# EAGLE.net
KiCad netlist of a schematic drawn in EAGLE
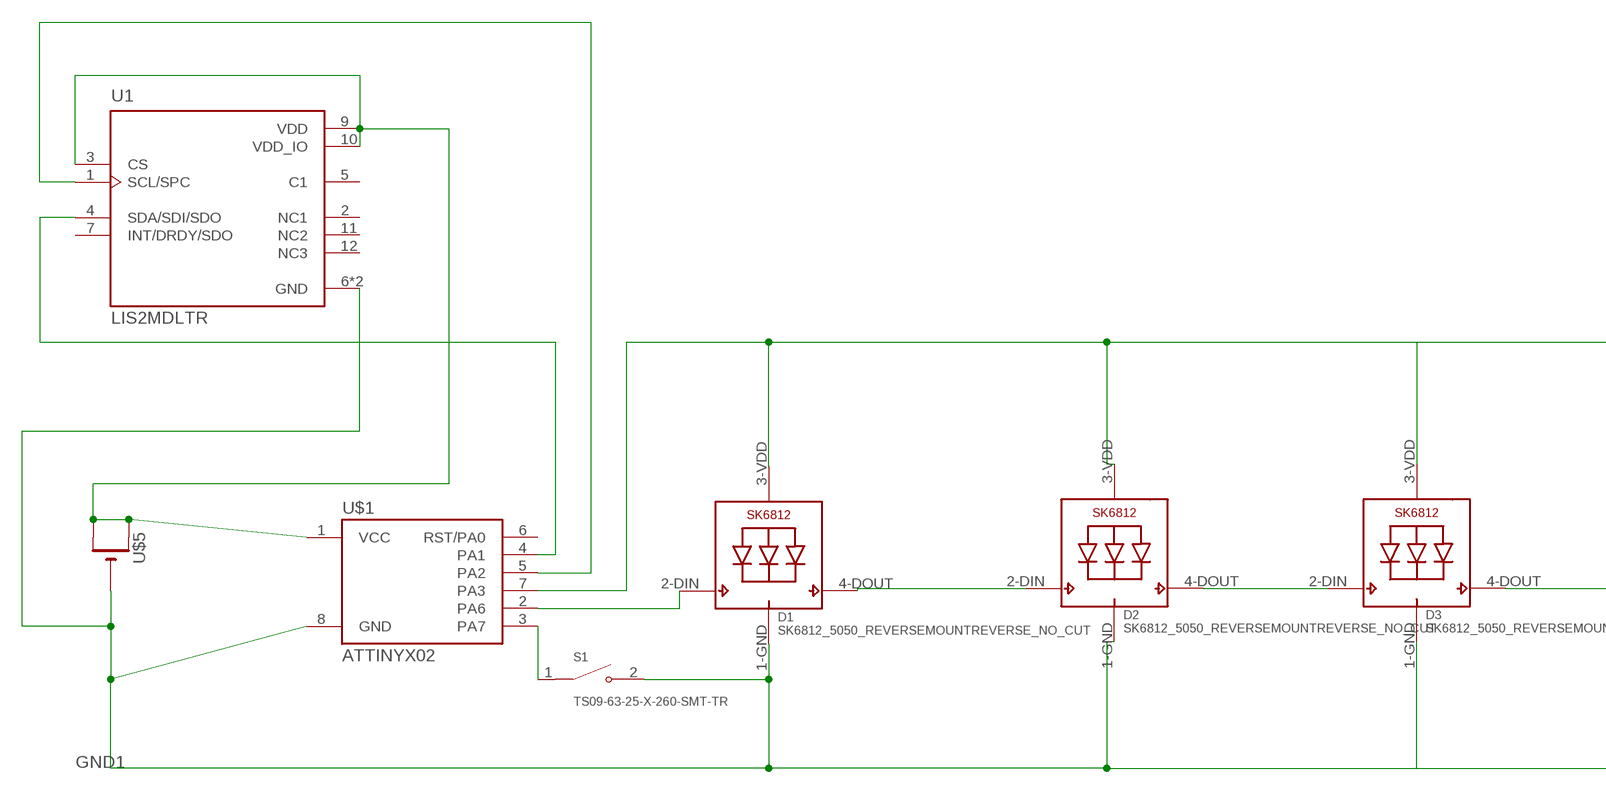
[diagram p0: schematic, sheet 1, part 1 of 2]
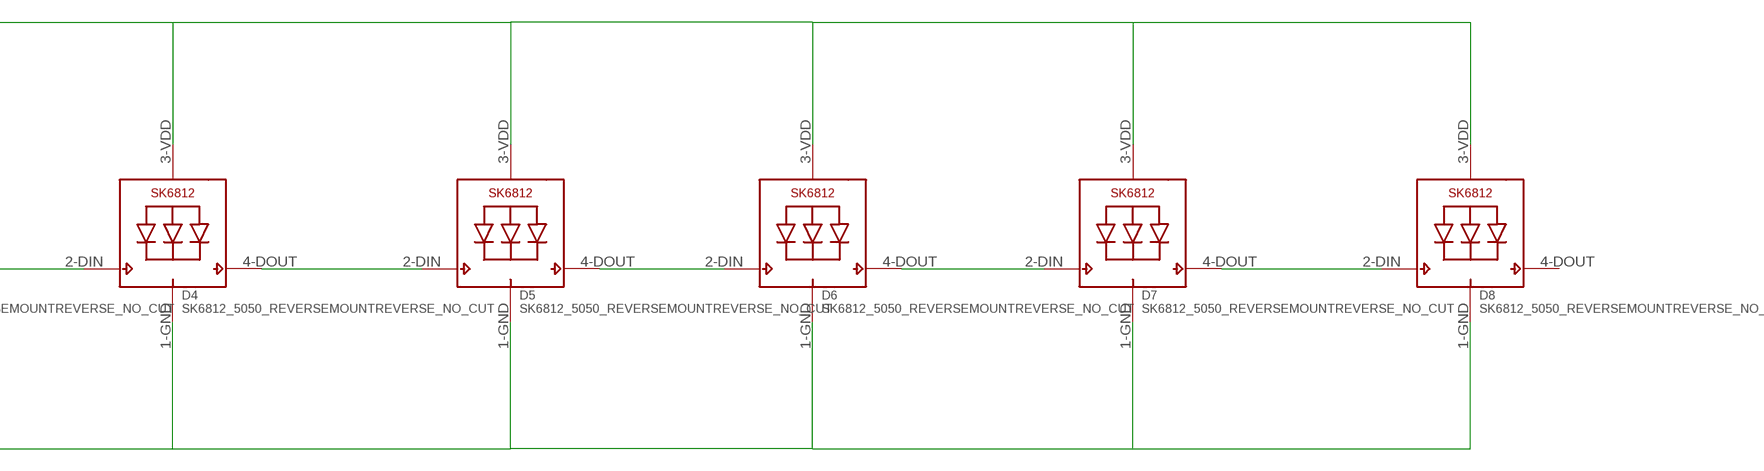
[diagram p1: schematic, sheet 1, part 2 of 2]

(export (version "E")
  (design (tool "Eeschema 10.0.6"))
  (components
    (comp (ref "D1")
      (value "SK6812_5050_REVERSEMOUNTREVERSE_NO_CUT")
      (footprint "eagle-import:SK6812_REVERSE_NO_CUT")
      (libsource (lib "eagle-import") (part "SK6812_5050_REVERSEMOUNTREVERSE_NO_CUT"))
    )
    (comp (ref "D2")
      (value "SK6812_5050_REVERSEMOUNTREVERSE_NO_CUT")
      (footprint "eagle-import:SK6812_REVERSE_NO_CUT")
      (libsource (lib "eagle-import") (part "SK6812_5050_REVERSEMOUNTREVERSE_NO_CUT"))
    )
    (comp (ref "D3")
      (value "SK6812_5050_REVERSEMOUNTREVERSE_NO_CUT")
      (footprint "eagle-import:SK6812_REVERSE_NO_CUT")
      (libsource (lib "eagle-import") (part "SK6812_5050_REVERSEMOUNTREVERSE_NO_CUT"))
    )
    (comp (ref "D4")
      (value "SK6812_5050_REVERSEMOUNTREVERSE_NO_CUT")
      (footprint "eagle-import:SK6812_REVERSE_NO_CUT")
      (libsource (lib "eagle-import") (part "SK6812_5050_REVERSEMOUNTREVERSE_NO_CUT"))
    )
    (comp (ref "D5")
      (value "SK6812_5050_REVERSEMOUNTREVERSE_NO_CUT")
      (footprint "eagle-import:SK6812_REVERSE_NO_CUT")
      (libsource (lib "eagle-import") (part "SK6812_5050_REVERSEMOUNTREVERSE_NO_CUT"))
    )
    (comp (ref "D6")
      (value "SK6812_5050_REVERSEMOUNTREVERSE_NO_CUT")
      (footprint "eagle-import:SK6812_REVERSE_NO_CUT")
      (libsource (lib "eagle-import") (part "SK6812_5050_REVERSEMOUNTREVERSE_NO_CUT"))
    )
    (comp (ref "D7")
      (value "SK6812_5050_REVERSEMOUNTREVERSE_NO_CUT")
      (footprint "eagle-import:SK6812_REVERSE_NO_CUT")
      (libsource (lib "eagle-import") (part "SK6812_5050_REVERSEMOUNTREVERSE_NO_CUT"))
    )
    (comp (ref "D8")
      (value "SK6812_5050_REVERSEMOUNTREVERSE_NO_CUT")
      (footprint "eagle-import:SK6812_REVERSE_NO_CUT")
      (libsource (lib "eagle-import") (part "SK6812_5050_REVERSEMOUNTREVERSE_NO_CUT"))
    )
    (comp (ref "S1")
      (value "TS09-63-25-X-260-SMT-TR")
      (footprint "eagle-import:SW_TS09-63-25-X-260-SMT-TR")
      (fields (field (name "MANUFACTURER") "CUI Devices"))
      (libsource (lib "eagle-import") (part "TS09-63-25-X-260-SMT-TR"))
    )
    (comp (ref "U$1")
      (value "ATTINYX02")
      (footprint "eagle-import:SOIC08_JEDEC_150MIL")
      (libsource (lib "eagle-import") (part "ATTINYX02"))
    )
    (comp (ref "U$5")
      (value "CR2032SMT")
      (footprint "eagle-import:CR2032-SMD")
      (libsource (lib "eagle-import") (part "CR2032SMT"))
    )
    (comp (ref "U1")
      (value "LIS2MDLTR")
      (footprint "eagle-import:PQFN50P200X200X70-12N")
      (fields (field (name "MF") "STMicroelectronics"))
      (libsource (lib "eagle-import") (part "LIS2MDLTR"))
    )
  )
  (nets
    (net (code "1") (name "/GND1") (class "Default")
      (node (ref "D1") (pin "1-GND") (pinfunction "GND_1-GND") (pintype "power_in"))
      (node (ref "D2") (pin "1-GND") (pinfunction "GND_1-GND") (pintype "power_in"))
      (node (ref "D3") (pin "1-GND") (pinfunction "GND_1-GND") (pintype "power_in"))
      (node (ref "D4") (pin "1-GND") (pinfunction "GND_1-GND") (pintype "power_in"))
      (node (ref "D5") (pin "1-GND") (pinfunction "GND_1-GND") (pintype "power_in"))
      (node (ref "D6") (pin "1-GND") (pinfunction "GND_1-GND") (pintype "power_in"))
      (node (ref "D7") (pin "1-GND") (pinfunction "GND_1-GND") (pintype "power_in"))
      (node (ref "D8") (pin "1-GND") (pinfunction "GND_1-GND") (pintype "power_in"))
      (node (ref "S1") (pin "2") (pinfunction "2_2") (pintype "passive"))
      (node (ref "U$1") (pin "8") (pinfunction "GND_8") (pintype "power_in"))
      (node (ref "U$5") (pin "-") (pinfunction "-_-") (pintype "passive"))
      (node (ref "U1") (pin "6") (pinfunction "GND_6") (pintype "power_in"))
      (node (ref "U1") (pin "8") (pinfunction "GND_8") (pintype "power_in"))
    )
    (net (code "2") (name "Net-(D1-DI)") (class "Default")
      (node (ref "D1") (pin "2-DIN") (pinfunction "DI_2-DIN") (pintype "input"))
      (node (ref "U$1") (pin "2") (pinfunction "PA6_2") (pintype "bidirectional"))
    )
    (net (code "3") (name "Net-(D1-DO)") (class "Default")
      (node (ref "D1") (pin "4-DOUT") (pinfunction "DO_4-DOUT") (pintype "output"))
      (node (ref "D2") (pin "2-DIN") (pinfunction "DI_2-DIN") (pintype "input"))
    )
    (net (code "4") (name "Net-(D1-VDD)") (class "Default")
      (node (ref "D1") (pin "3-VDD") (pinfunction "VDD_3-VDD") (pintype "power_in"))
      (node (ref "D2") (pin "3-VDD") (pinfunction "VDD_3-VDD") (pintype "power_in"))
      (node (ref "D3") (pin "3-VDD") (pinfunction "VDD_3-VDD") (pintype "power_in"))
      (node (ref "D4") (pin "3-VDD") (pinfunction "VDD_3-VDD") (pintype "power_in"))
      (node (ref "D5") (pin "3-VDD") (pinfunction "VDD_3-VDD") (pintype "power_in"))
      (node (ref "D6") (pin "3-VDD") (pinfunction "VDD_3-VDD") (pintype "power_in"))
      (node (ref "D7") (pin "3-VDD") (pinfunction "VDD_3-VDD") (pintype "power_in"))
      (node (ref "D8") (pin "3-VDD") (pinfunction "VDD_3-VDD") (pintype "power_in"))
      (node (ref "U$1") (pin "7") (pinfunction "PA3_7") (pintype "bidirectional"))
    )
    (net (code "5") (name "Net-(D2-DO)") (class "Default")
      (node (ref "D2") (pin "4-DOUT") (pinfunction "DO_4-DOUT") (pintype "output"))
      (node (ref "D3") (pin "2-DIN") (pinfunction "DI_2-DIN") (pintype "input"))
    )
    (net (code "6") (name "Net-(D3-DO)") (class "Default")
      (node (ref "D3") (pin "4-DOUT") (pinfunction "DO_4-DOUT") (pintype "output"))
      (node (ref "D4") (pin "2-DIN") (pinfunction "DI_2-DIN") (pintype "input"))
    )
    (net (code "7") (name "Net-(D4-DO)") (class "Default")
      (node (ref "D4") (pin "4-DOUT") (pinfunction "DO_4-DOUT") (pintype "output"))
      (node (ref "D5") (pin "2-DIN") (pinfunction "DI_2-DIN") (pintype "input"))
    )
    (net (code "8") (name "Net-(D5-DO)") (class "Default")
      (node (ref "D5") (pin "4-DOUT") (pinfunction "DO_4-DOUT") (pintype "output"))
      (node (ref "D6") (pin "2-DIN") (pinfunction "DI_2-DIN") (pintype "input"))
    )
    (net (code "9") (name "Net-(D6-DO)") (class "Default")
      (node (ref "D6") (pin "4-DOUT") (pinfunction "DO_4-DOUT") (pintype "output"))
      (node (ref "D7") (pin "2-DIN") (pinfunction "DI_2-DIN") (pintype "input"))
    )
    (net (code "10") (name "Net-(D7-DO)") (class "Default")
      (node (ref "D7") (pin "4-DOUT") (pinfunction "DO_4-DOUT") (pintype "output"))
      (node (ref "D8") (pin "2-DIN") (pinfunction "DI_2-DIN") (pintype "input"))
    )
    (net (code "11") (name "Net-(U$1-PA1)") (class "Default")
      (node (ref "U$1") (pin "4") (pinfunction "PA1_4") (pintype "bidirectional"))
      (node (ref "U1") (pin "4") (pinfunction "SDA/SDI/SDO_4") (pintype "bidirectional"))
    )
    (net (code "12") (name "Net-(U$1-PA2)") (class "Default")
      (node (ref "U$1") (pin "5") (pinfunction "PA2_5") (pintype "bidirectional"))
      (node (ref "U1") (pin "1") (pinfunction "SCL/SPC_1") (pintype "input"))
    )
    (net (code "13") (name "Net-(U$1-PA7)") (class "Default")
      (node (ref "S1") (pin "1") (pinfunction "1_1") (pintype "passive"))
      (node (ref "U$1") (pin "3") (pinfunction "PA7_3") (pintype "bidirectional"))
    )
    (net (code "14") (name "Net-(U$1-VCC)") (class "Default")
      (node (ref "U$1") (pin "1") (pinfunction "VCC_1") (pintype "power_in"))
      (node (ref "U$5") (pin "+$1") (pinfunction "+_+$1") (pintype "passive"))
      (node (ref "U$5") (pin "+$2") (pinfunction "+1_+$2") (pintype "passive"))
      (node (ref "U1") (pin "10") (pinfunction "VDD_IO_10") (pintype "power_in"))
      (node (ref "U1") (pin "3") (pinfunction "CS_3") (pintype "input"))
      (node (ref "U1") (pin "9") (pinfunction "VDD_9") (pintype "power_in"))
    )
    (net (code "15") (name "unconnected-(D8-DO-Pad4-DOUT)") (class "Default")
      (node (ref "D8") (pin "4-DOUT") (pinfunction "DO_4-DOUT") (pintype "output"))
    )
    (net (code "16") (name "unconnected-(U$1-RST{slash}PA0-Pad6)") (class "Default")
      (node (ref "U$1") (pin "6") (pinfunction "RST/PA0_6") (pintype "bidirectional"))
    )
    (net (code "17") (name "unconnected-(U1-C1-Pad5)") (class "Default")
      (node (ref "U1") (pin "5") (pinfunction "C1_5") (pintype "passive"))
    )
    (net (code "18") (name "unconnected-(U1-INT{slash}DRDY{slash}SDO-Pad7)") (class "Default")
      (node (ref "U1") (pin "7") (pinfunction "INT/DRDY/SDO_7") (pintype "bidirectional"))
    )
    (net (code "19") (name "unconnected-(U1-NC1-Pad2)") (class "Default")
      (node (ref "U1") (pin "2") (pinfunction "NC1_2") (pintype "passive"))
    )
    (net (code "20") (name "unconnected-(U1-NC2-Pad11)") (class "Default")
      (node (ref "U1") (pin "11") (pinfunction "NC2_11") (pintype "passive"))
    )
    (net (code "21") (name "unconnected-(U1-NC3-Pad12)") (class "Default")
      (node (ref "U1") (pin "12") (pinfunction "NC3_12") (pintype "passive"))
    )
  )
)
